# BNO055.net
KiCad netlist of a schematic drawn in Altium Designer
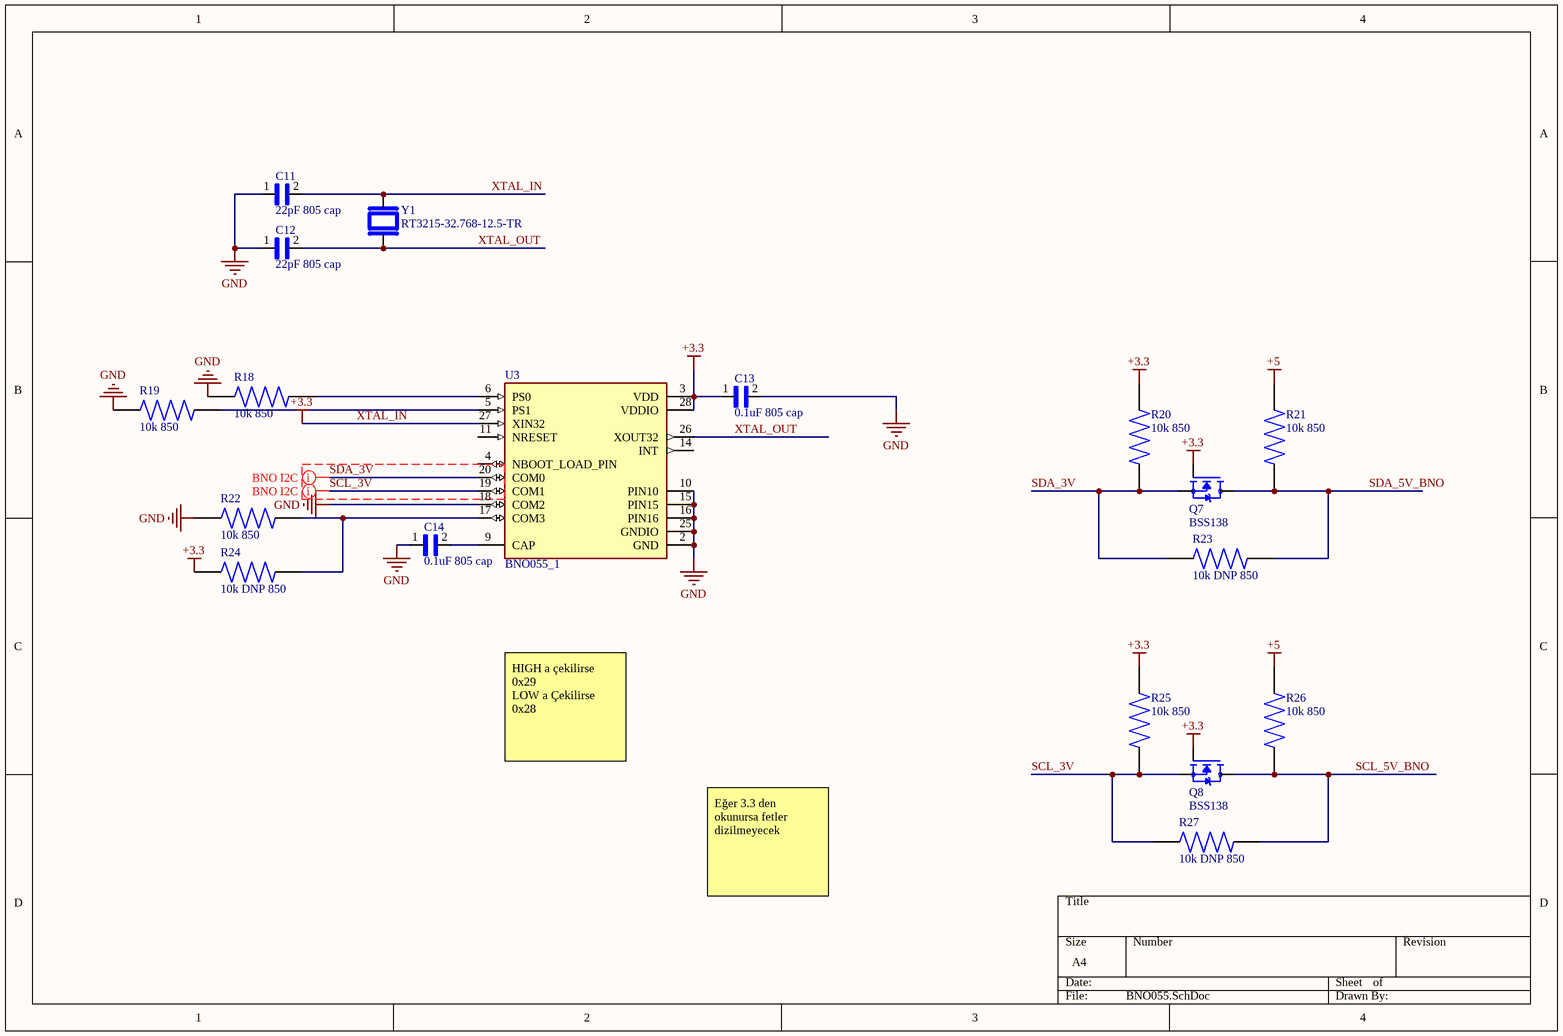
[diagram p0: BNO055.SchDoc]

(export (version "E")
  (design (tool "Eeschema 10.0.6"))
  (components
    (comp (ref "C11")
      (value "22pF 805 cap")
      (footprint "1uF 805 Cap")
      (libsource (lib "iee_altium") (part "1uF 805 cap"))
    )
    (comp (ref "C12")
      (value "22pF 805 cap")
      (footprint "1uF 805 Cap")
      (libsource (lib "iee_altium") (part "1uF 805 cap"))
    )
    (comp (ref "C13")
      (value "0.1uF 805 cap")
      (footprint "1uF 805 Cap")
      (libsource (lib "iee_altium") (part "1uF 805 cap"))
    )
    (comp (ref "C14")
      (value "0.1uF 805 cap")
      (footprint "1uF 805 Cap")
      (libsource (lib "iee_altium") (part "1uF 805 cap"))
    )
    (comp (ref "Q7")
      (value "BSS138")
      (footprint "SOT91P240X110-3N - duplicate")
      (description "N-Channel 50 V 220mA (Ta) 350mW (Ta) Surface Mount SOT-23-3")
      (fields (field (name "MF") "onsemi"))
      (libsource (lib "iee_altium") (part "BSS138"))
    )
    (comp (ref "Q8")
      (value "BSS138")
      (footprint "SOT91P240X110-3N - duplicate")
      (description "N-Channel 50 V 220mA (Ta) 350mW (Ta) Surface Mount SOT-23-3")
      (fields (field (name "MF") "onsemi"))
      (libsource (lib "iee_altium") (part "BSS138"))
    )
    (comp (ref "R18") (value "10k 850") (footprint "10k 850") (libsource (lib "iee_altium") (part "10k 850")))
    (comp (ref "R19") (value "10k 850") (footprint "10k 850") (libsource (lib "iee_altium") (part "10k 850")))
    (comp (ref "R20") (value "10k 850") (footprint "10k 850") (libsource (lib "iee_altium") (part "10k 850")))
    (comp (ref "R21") (value "10k 850") (footprint "10k 850") (libsource (lib "iee_altium") (part "10k 850")))
    (comp (ref "R22") (value "10k 850") (footprint "10k 850") (libsource (lib "iee_altium") (part "10k 850")))
    (comp (ref "R23")
      (value "10k DNP 850")
      (footprint "10k 850")
      (libsource (lib "iee_altium") (part "10k 850"))
    )
    (comp (ref "R24")
      (value "10k DNP 850")
      (footprint "10k 850")
      (libsource (lib "iee_altium") (part "10k 850"))
    )
    (comp (ref "R25") (value "10k 850") (footprint "10k 850") (libsource (lib "iee_altium") (part "10k 850")))
    (comp (ref "R26") (value "10k 850") (footprint "10k 850") (libsource (lib "iee_altium") (part "10k 850")))
    (comp (ref "R27")
      (value "10k DNP 850")
      (footprint "10k 850")
      (libsource (lib "iee_altium") (part "10k 850"))
    )
    (comp (ref "U3")
      (value "BNO055_1")
      (footprint "LGA28R50P4X10_380X520X100")
      (description "BNO055 9-axis Absolute Orientation Sensor ( SiP ) w/Sensors and Sensor Fusion")
      (fields (field (name "MP") "BNO055"))
      (libsource (lib "iee_altium") (part "BNO055_1"))
    )
    (comp (ref "Y1")
      (value "RT3215-32.768-12.5-TR")
      (footprint "XTAL_RT3215-32.768-12.5-TR")
      (description "32.768 kHz Â±20ppm Crystal 12.5pF 70 kOhms 2-SMD, No Lead")
      (fields (field (name "MF") "Raltron Electronics"))
      (libsource (lib "iee_altium") (part "RT3215-32.768-12.5-TR"))
    )
  )
  (nets
    (net (code "1") (name "+3.3") (class "Default")
      (node (ref "C11") (pin "2") (pinfunction "2_2") (pintype "passive"))
      (node (ref "C13") (pin "1") (pinfunction "1_1") (pintype "passive"))
      (node (ref "Q7") (pin "1") (pinfunction "G_1") (pintype "passive"))
      (node (ref "Q8") (pin "1") (pinfunction "G_1") (pintype "passive"))
      (node (ref "R20") (pin "1") (pinfunction "1_1") (pintype "passive"))
      (node (ref "R24") (pin "1") (pinfunction "1_1") (pintype "passive"))
      (node (ref "R25") (pin "1") (pinfunction "1_1") (pintype "passive"))
      (node (ref "U3") (pin "27") (pinfunction "XIN32_27") (pintype "input"))
      (node (ref "U3") (pin "28") (pinfunction "VDDIO_28") (pintype "power_in"))
      (node (ref "U3") (pin "3") (pinfunction "VDD_3") (pintype "power_in"))
      (node (ref "Y1") (pin "1") (pinfunction "1_1") (pintype "passive"))
    )
    (net (code "2") (name "+5") (class "Default")
      (node (ref "R21") (pin "1") (pinfunction "1_1") (pintype "passive"))
      (node (ref "R26") (pin "1") (pinfunction "1_1") (pintype "passive"))
    )
    (net (code "3") (name "/SCL_3V") (class "Default")
      (node (ref "Q8") (pin "2") (pinfunction "S_2") (pintype "passive"))
      (node (ref "R25") (pin "2") (pinfunction "2_2") (pintype "passive"))
      (node (ref "R27") (pin "1") (pinfunction "1_1") (pintype "passive"))
      (node (ref "U3") (pin "19") (pinfunction "COM1_19") (pintype "bidirectional"))
    )
    (net (code "4") (name "/SCL_5V_BNO") (class "Default")
      (node (ref "Q8") (pin "3") (pinfunction "D_3") (pintype "passive"))
      (node (ref "R26") (pin "2") (pinfunction "2_2") (pintype "passive"))
      (node (ref "R27") (pin "2") (pinfunction "2_2") (pintype "passive"))
    )
    (net (code "5") (name "/SDA_3V") (class "Default")
      (node (ref "Q7") (pin "2") (pinfunction "S_2") (pintype "passive"))
      (node (ref "R20") (pin "2") (pinfunction "2_2") (pintype "passive"))
      (node (ref "R23") (pin "1") (pinfunction "1_1") (pintype "passive"))
      (node (ref "U3") (pin "20") (pinfunction "COM0_20") (pintype "bidirectional"))
    )
    (net (code "6") (name "/SDA_5V_BNO") (class "Default")
      (node (ref "Q7") (pin "3") (pinfunction "D_3") (pintype "passive"))
      (node (ref "R21") (pin "2") (pinfunction "2_2") (pintype "passive"))
      (node (ref "R23") (pin "2") (pinfunction "2_2") (pintype "passive"))
    )
    (net (code "7") (name "/XTAL_OUT") (class "Default")
      (node (ref "C12") (pin "2") (pinfunction "2_2") (pintype "passive"))
      (node (ref "U3") (pin "26") (pinfunction "XOUT32_26") (pintype "output"))
      (node (ref "Y1") (pin "2") (pinfunction "2_2") (pintype "passive"))
    )
    (net (code "8") (name "GND") (class "Default")
      (node (ref "C11") (pin "1") (pinfunction "1_1") (pintype "passive"))
      (node (ref "C12") (pin "1") (pinfunction "1_1") (pintype "passive"))
      (node (ref "C13") (pin "2") (pinfunction "2_2") (pintype "passive"))
      (node (ref "C14") (pin "1") (pinfunction "1_1") (pintype "passive"))
      (node (ref "R18") (pin "1") (pinfunction "1_1") (pintype "passive"))
      (node (ref "R19") (pin "1") (pinfunction "1_1") (pintype "passive"))
      (node (ref "R22") (pin "1") (pinfunction "1_1") (pintype "passive"))
      (node (ref "U3") (pin "10") (pinfunction "PIN10_10") (pintype "power_in"))
      (node (ref "U3") (pin "15") (pinfunction "PIN15_15") (pintype "power_in"))
      (node (ref "U3") (pin "16") (pinfunction "PIN16_16") (pintype "power_in"))
      (node (ref "U3") (pin "18") (pinfunction "COM2_18") (pintype "bidirectional"))
      (node (ref "U3") (pin "2") (pinfunction "GND_2") (pintype "power_in"))
      (node (ref "U3") (pin "25") (pinfunction "GNDIO_25") (pintype "power_in"))
    )
    (net (code "9") (name "Net-(U3-CAP)") (class "Default")
      (node (ref "C14") (pin "2") (pinfunction "2_2") (pintype "passive"))
      (node (ref "U3") (pin "9") (pinfunction "CAP_9") (pintype "passive"))
    )
    (net (code "10") (name "Net-(U3-COM3)") (class "Default")
      (node (ref "R22") (pin "2") (pinfunction "2_2") (pintype "passive"))
      (node (ref "R24") (pin "2") (pinfunction "2_2") (pintype "passive"))
      (node (ref "U3") (pin "17") (pinfunction "COM3_17") (pintype "bidirectional"))
    )
    (net (code "11") (name "Net-(U3-PS0)") (class "Default")
      (node (ref "R18") (pin "2") (pinfunction "2_2") (pintype "passive"))
      (node (ref "U3") (pin "6") (pinfunction "PS0_6") (pintype "input"))
    )
    (net (code "12") (name "Net-(U3-PS1)") (class "Default")
      (node (ref "R19") (pin "2") (pinfunction "2_2") (pintype "passive"))
      (node (ref "U3") (pin "5") (pinfunction "PS1_5") (pintype "input"))
    )
    (net (code "13") (name "unconnected-(U3-INT-Pad14)") (class "Default")
      (node (ref "U3") (pin "14") (pinfunction "INT_14") (pintype "output"))
    )
    (net (code "14") (name "unconnected-(U3-NBOOT_LOAD_PIN-Pad4)") (class "Default")
      (node (ref "U3") (pin "4") (pinfunction "NBOOT_LOAD_PIN_4") (pintype "bidirectional"))
    )
    (net (code "15") (name "unconnected-(U3-NRESET-Pad11)") (class "Default")
      (node (ref "U3") (pin "11") (pinfunction "NRESET_11") (pintype "input"))
    )
  )
)
